# POWER.net
KiCad netlist of a schematic drawn in Altium Designer
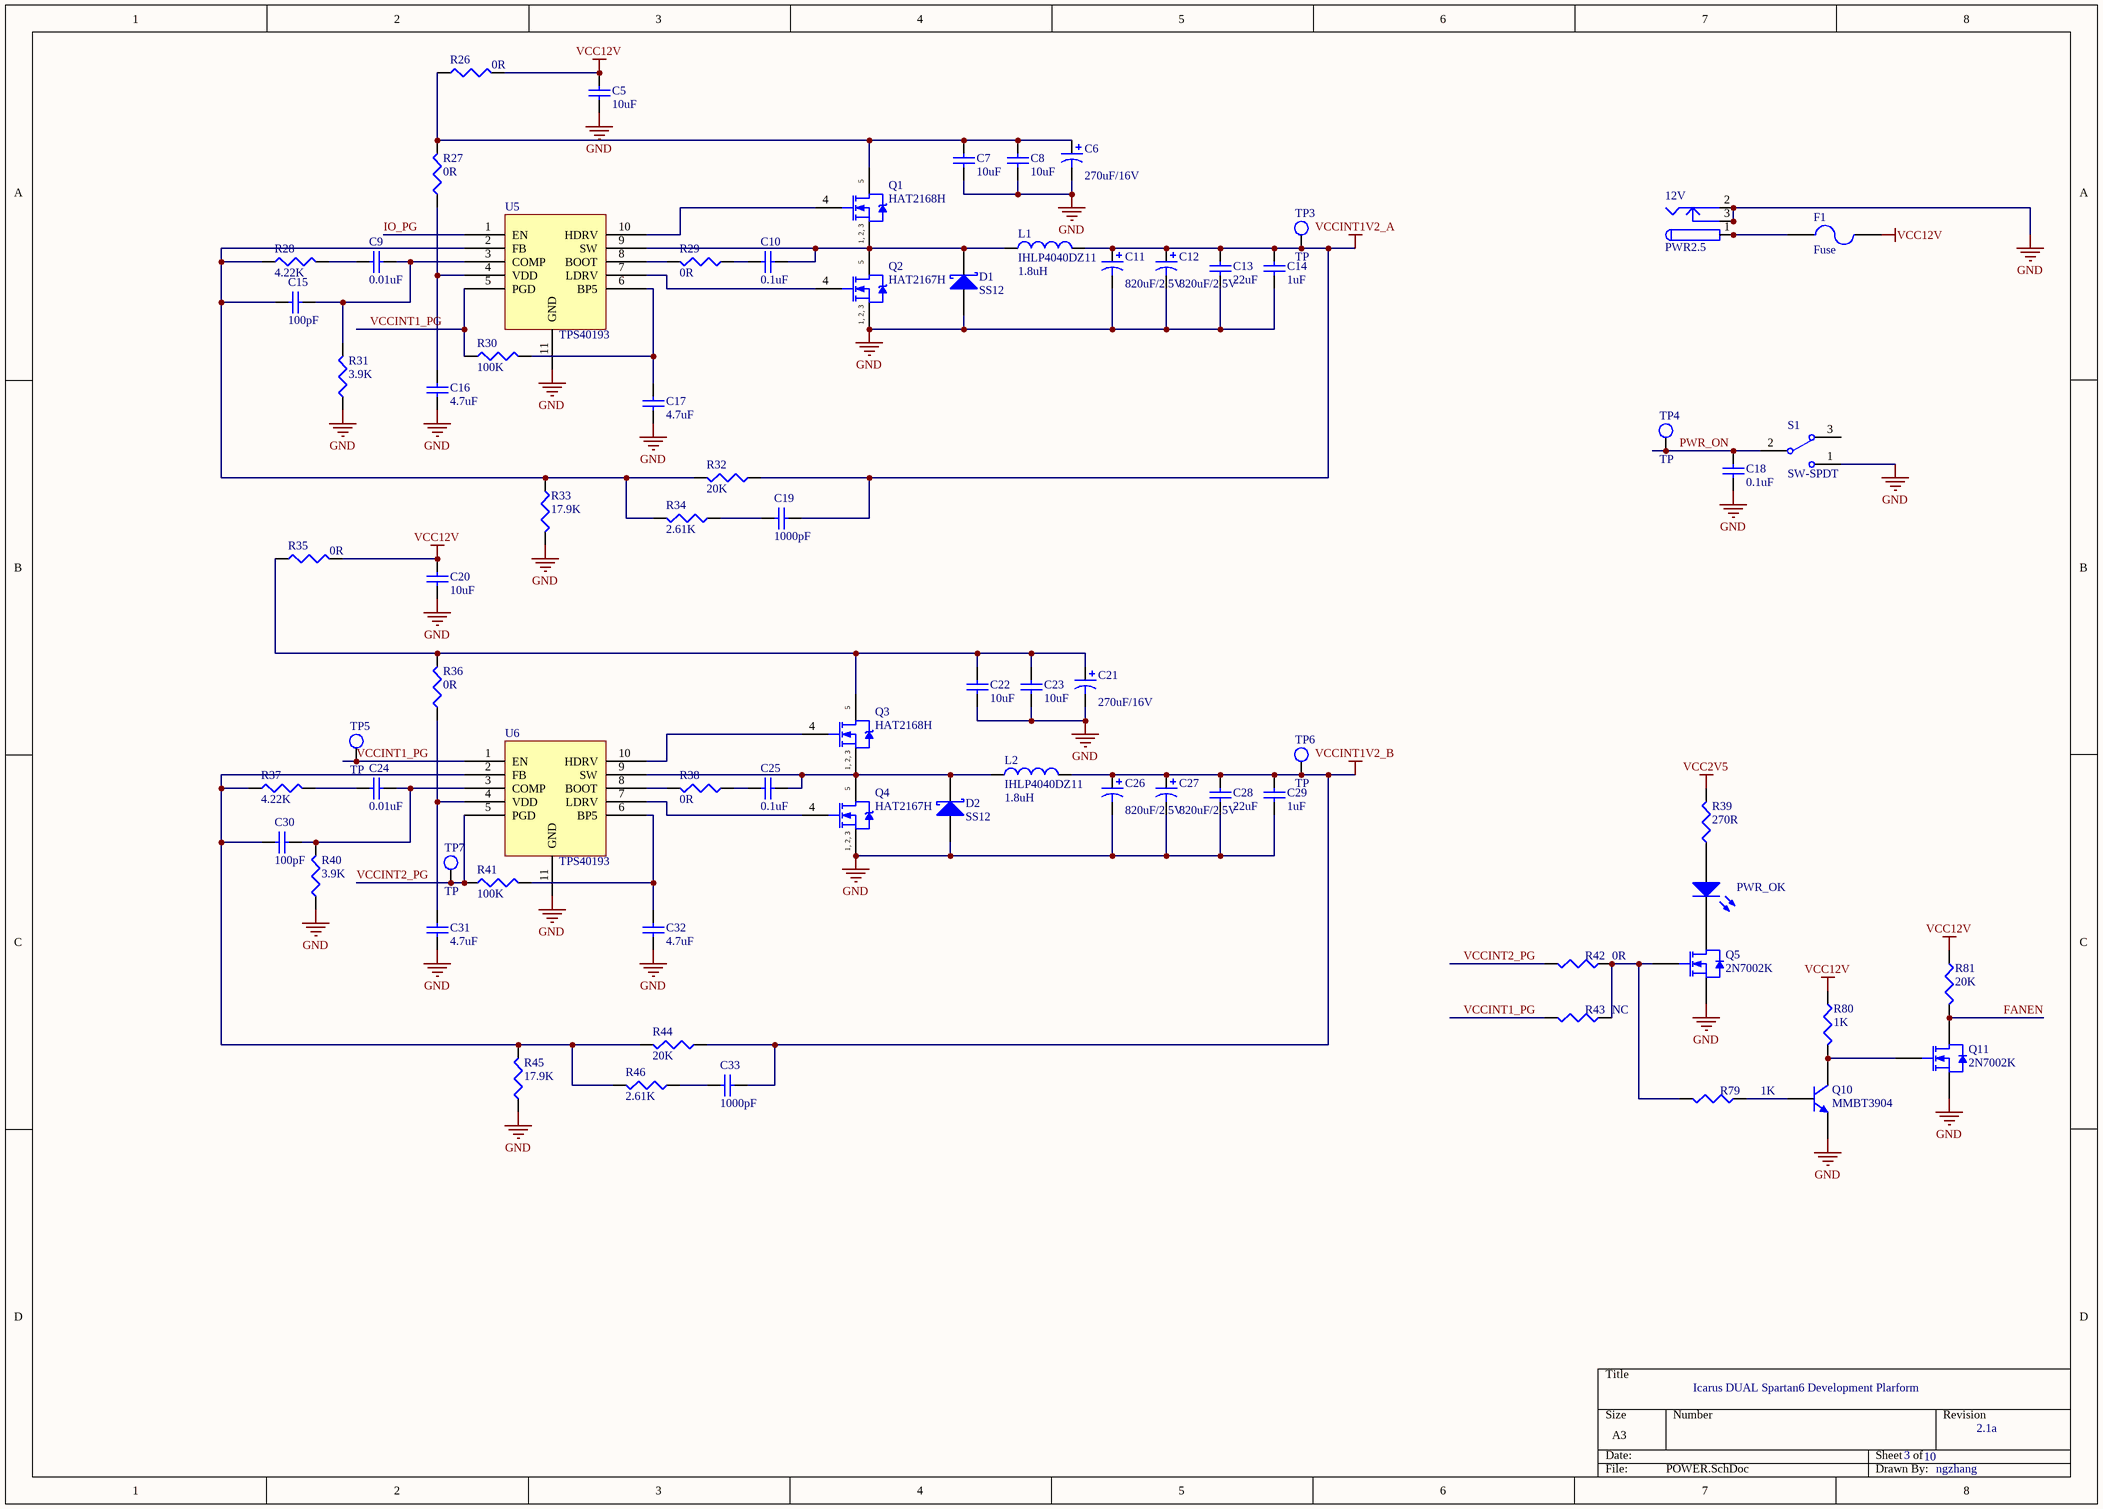
[diagram p0: POWER.SchDoc]

(export (version "E")
  (design (tool "Eeschema 10.0.6"))
  (components
    (comp (ref "12V")
      (value "PWR2.5")
      (footprint "KLD-0202")
      (description "Low Voltage Power Supply Connector")
      (fields (field (name "PUBLISHER") "Altium Limited"))
      (libsource (lib "Miscellaneous Connectors") (part "PWR2.5"))
    )
    (comp (ref "C5")
      (value "10uF")
      (footprint "C1206")
      (description "Capacitor (Semiconductor SIM Model)")
      (fields (field (name "PUBLISHER") "Altium Limited"))
      (libsource (lib "Miscellaneous Devices") (part "Cap Semi"))
    )
    (comp (ref "C6")
      (value "270uF/16V")
      (footprint "CAP8X8")
      (description "Polarized Capacitor (Radial)")
      (fields (field (name "PUBLISHER") "Altium Limited"))
      (libsource (lib "Miscellaneous Devices") (part "Cap Pol1"))
    )
    (comp (ref "C7")
      (value "10uF")
      (footprint "C1206")
      (description "Capacitor (Semiconductor SIM Model)")
      (fields (field (name "PUBLISHER") "Altium Limited"))
      (libsource (lib "Miscellaneous Devices") (part "Cap Semi"))
    )
    (comp (ref "C8")
      (value "10uF")
      (footprint "C1206")
      (description "Capacitor (Semiconductor SIM Model)")
      (fields (field (name "PUBLISHER") "Altium Limited"))
      (libsource (lib "Miscellaneous Devices") (part "Cap Semi"))
    )
    (comp (ref "C9")
      (value "0.01uF")
      (footprint "1608[0603]")
      (description "Capacitor (Semiconductor SIM Model)")
      (fields (field (name "PUBLISHER") "Altium Limited"))
      (libsource (lib "Miscellaneous Devices") (part "Cap Semi"))
    )
    (comp (ref "C10")
      (value "0.1uF")
      (footprint "1608[0603]")
      (description "Capacitor (Semiconductor SIM Model)")
      (fields (field (name "PUBLISHER") "Altium Limited"))
      (libsource (lib "Miscellaneous Devices") (part "Cap Semi"))
    )
    (comp (ref "C11")
      (value "820uF/2.5V")
      (footprint "CAP8X8")
      (description "Polarized Capacitor (Radial)")
      (fields (field (name "PUBLISHER") "Altium Limited"))
      (libsource (lib "Miscellaneous Devices") (part "Cap Pol1"))
    )
    (comp (ref "C12")
      (value "820uF/2.5V")
      (footprint "CAP8X8")
      (description "Polarized Capacitor (Radial)")
      (fields (field (name "PUBLISHER") "Altium Limited"))
      (libsource (lib "Miscellaneous Devices") (part "Cap Pol1"))
    )
    (comp (ref "C13")
      (value "22uF")
      (footprint "C1206")
      (description "Capacitor (Semiconductor SIM Model)")
      (fields (field (name "PUBLISHER") "Altium Limited"))
      (libsource (lib "Miscellaneous Devices") (part "Cap Semi"))
    )
    (comp (ref "C14")
      (value "1uF")
      (footprint "1608[0603]")
      (description "Capacitor (Semiconductor SIM Model)")
      (fields (field (name "PUBLISHER") "Altium Limited"))
      (libsource (lib "Miscellaneous Devices") (part "Cap Semi"))
    )
    (comp (ref "C15")
      (value "100pF")
      (footprint "1608[0603]")
      (description "Capacitor (Semiconductor SIM Model)")
      (fields (field (name "PUBLISHER") "Altium Limited"))
      (libsource (lib "Miscellaneous Devices") (part "Cap Semi"))
    )
    (comp (ref "C16")
      (value "4.7uF")
      (footprint "C0805")
      (description "Capacitor (Semiconductor SIM Model)")
      (fields (field (name "PUBLISHER") "Altium Limited"))
      (libsource (lib "Miscellaneous Devices") (part "Cap Semi"))
    )
    (comp (ref "C17")
      (value "4.7uF")
      (footprint "C0805")
      (description "Capacitor (Semiconductor SIM Model)")
      (fields (field (name "PUBLISHER") "Altium Limited"))
      (libsource (lib "Miscellaneous Devices") (part "Cap Semi"))
    )
    (comp (ref "C18")
      (value "0.1uF")
      (footprint "1608[0603]")
      (description "Capacitor (Semiconductor SIM Model)")
      (fields (field (name "PUBLISHER") "Altium Limited"))
      (libsource (lib "Miscellaneous Devices") (part "Cap Semi"))
    )
    (comp (ref "C19")
      (value "1000pF")
      (footprint "1608[0603]")
      (description "Capacitor (Semiconductor SIM Model)")
      (fields (field (name "PUBLISHER") "Altium Limited"))
      (libsource (lib "Miscellaneous Devices") (part "Cap Semi"))
    )
    (comp (ref "C20")
      (value "10uF")
      (footprint "C1206")
      (description "Capacitor (Semiconductor SIM Model)")
      (fields (field (name "PUBLISHER") "Altium Limited"))
      (libsource (lib "Miscellaneous Devices") (part "Cap Semi"))
    )
    (comp (ref "C21")
      (value "270uF/16V")
      (footprint "CAP8X8")
      (description "Polarized Capacitor (Radial)")
      (fields (field (name "PUBLISHER") "Altium Limited"))
      (libsource (lib "Miscellaneous Devices") (part "Cap Pol1"))
    )
    (comp (ref "C22")
      (value "10uF")
      (footprint "C1206")
      (description "Capacitor (Semiconductor SIM Model)")
      (fields (field (name "PUBLISHER") "Altium Limited"))
      (libsource (lib "Miscellaneous Devices") (part "Cap Semi"))
    )
    (comp (ref "C23")
      (value "10uF")
      (footprint "C1206")
      (description "Capacitor (Semiconductor SIM Model)")
      (fields (field (name "PUBLISHER") "Altium Limited"))
      (libsource (lib "Miscellaneous Devices") (part "Cap Semi"))
    )
    (comp (ref "C24")
      (value "0.01uF")
      (footprint "1608[0603]")
      (description "Capacitor (Semiconductor SIM Model)")
      (fields (field (name "PUBLISHER") "Altium Limited"))
      (libsource (lib "Miscellaneous Devices") (part "Cap Semi"))
    )
    (comp (ref "C25")
      (value "0.1uF")
      (footprint "1608[0603]")
      (description "Capacitor (Semiconductor SIM Model)")
      (fields (field (name "PUBLISHER") "Altium Limited"))
      (libsource (lib "Miscellaneous Devices") (part "Cap Semi"))
    )
    (comp (ref "C26")
      (value "820uF/2.5V")
      (footprint "CAP8X8")
      (description "Polarized Capacitor (Radial)")
      (fields (field (name "PUBLISHER") "Altium Limited"))
      (libsource (lib "Miscellaneous Devices") (part "Cap Pol1"))
    )
    (comp (ref "C27")
      (value "820uF/2.5V")
      (footprint "CAP8X8")
      (description "Polarized Capacitor (Radial)")
      (fields (field (name "PUBLISHER") "Altium Limited"))
      (libsource (lib "Miscellaneous Devices") (part "Cap Pol1"))
    )
    (comp (ref "C28")
      (value "22uF")
      (footprint "C1206")
      (description "Capacitor (Semiconductor SIM Model)")
      (fields (field (name "PUBLISHER") "Altium Limited"))
      (libsource (lib "Miscellaneous Devices") (part "Cap Semi"))
    )
    (comp (ref "C29")
      (value "1uF")
      (footprint "1608[0603]")
      (description "Capacitor (Semiconductor SIM Model)")
      (fields (field (name "PUBLISHER") "Altium Limited"))
      (libsource (lib "Miscellaneous Devices") (part "Cap Semi"))
    )
    (comp (ref "C30")
      (value "100pF")
      (footprint "1608[0603]")
      (description "Capacitor (Semiconductor SIM Model)")
      (fields (field (name "PUBLISHER") "Altium Limited"))
      (libsource (lib "Miscellaneous Devices") (part "Cap Semi"))
    )
    (comp (ref "C31")
      (value "4.7uF")
      (footprint "C0805")
      (description "Capacitor (Semiconductor SIM Model)")
      (fields (field (name "PUBLISHER") "Altium Limited"))
      (libsource (lib "Miscellaneous Devices") (part "Cap Semi"))
    )
    (comp (ref "C32")
      (value "4.7uF")
      (footprint "C0805")
      (description "Capacitor (Semiconductor SIM Model)")
      (fields (field (name "PUBLISHER") "Altium Limited"))
      (libsource (lib "Miscellaneous Devices") (part "Cap Semi"))
    )
    (comp (ref "C33")
      (value "1000pF")
      (footprint "1608[0603]")
      (description "Capacitor (Semiconductor SIM Model)")
      (fields (field (name "PUBLISHER") "Altium Limited"))
      (libsource (lib "Miscellaneous Devices") (part "Cap Semi"))
    )
    (comp (ref "D1")
      (value "SS12")
      (footprint "SMA")
      (description "Schottky Rectifier")
      (fields (field (name "PUBLISHER") "Altium Limited"))
      (libsource (lib "IR Rectifier - Schottky") (part "10MQ060N"))
    )
    (comp (ref "D2")
      (value "SS12")
      (footprint "SMA")
      (description "Schottky Rectifier")
      (fields (field (name "PUBLISHER") "Altium Limited"))
      (libsource (lib "IR Rectifier - Schottky") (part "10MQ060N"))
    )
    (comp (ref "F1")
      (value "Fuse")
      (footprint "12Z-2010")
      (fields (field (name "PUBLISHER") "Altium Limited"))
      (libsource (lib "Miscellaneous Devices") (part "Fuse 2"))
    )
    (comp (ref "L1")
      (value "IHLP4040DZ11")
      (footprint "IHLP4040")
      (description "Inductor")
      (fields (field (name "ALTIUM_VALUE") "1.8uH") (field (name "PUBLISHER") "Altium Limited"))
      (libsource (lib "Miscellaneous Devices") (part "Inductor"))
    )
    (comp (ref "L2")
      (value "IHLP4040DZ11")
      (footprint "IHLP4040")
      (description "Inductor")
      (fields (field (name "ALTIUM_VALUE") "1.8uH") (field (name "PUBLISHER") "Altium Limited"))
      (libsource (lib "Miscellaneous Devices") (part "Inductor"))
    )
    (comp (ref "PWR_OK")
      (value "LED3")
      (footprint "CD1608-0603")
      (description "Typical BLUE SiC LED")
      (fields (field (name "PUBLISHER") "Altium Limited"))
      (libsource (lib "Miscellaneous Devices") (part "LED3"))
    )
    (comp (ref "Q1") (value "HAT2168H") (footprint "LFPAK") (libsource (lib "S6") (part "HAT216X")))
    (comp (ref "Q2") (value "HAT2167H") (footprint "LFPAK") (libsource (lib "S6") (part "HAT216X")))
    (comp (ref "Q3") (value "HAT2168H") (footprint "LFPAK") (libsource (lib "S6") (part "HAT216X")))
    (comp (ref "Q4") (value "HAT2167H") (footprint "LFPAK") (libsource (lib "S6") (part "HAT216X")))
    (comp (ref "Q5")
      (value "2N7002K")
      (footprint "SOT23_N")
      (description "N-channel Enhancement Mode Field-effect Transistor")
      (fields (field (name "PUBLISHER") "Altium Limited"))
      (libsource (lib "Philips Discrete MOSFET - Low Power") (part "2N7002"))
    )
    (comp (ref "Q10")
      (value "MMBT3904")
      (footprint "SOT23_N")
      (description "NPN Switching Transistor")
      (fields (field (name "PUBLISHER") "Altium Limited"))
      (libsource (lib "Philips Discrete BJT - Low Power") (part "MMBT3904"))
    )
    (comp (ref "Q11")
      (value "2N7002K")
      (footprint "SOT23_N")
      (description "N-channel Enhancement Mode Field-effect Transistor")
      (fields (field (name "PUBLISHER") "Altium Limited"))
      (libsource (lib "Philips Discrete MOSFET - Low Power") (part "2N7002"))
    )
    (comp (ref "R26")
      (value "0R")
      (footprint "C1206")
      (description "Resistor")
      (fields (field (name "PUBLISHER") "Altium Limited"))
      (libsource (lib "Miscellaneous Devices") (part "Res3"))
    )
    (comp (ref "R27")
      (value "0R")
      (footprint "J1-0603")
      (description "Resistor")
      (fields (field (name "PUBLISHER") "Altium Limited"))
      (libsource (lib "Miscellaneous Devices") (part "Res3"))
    )
    (comp (ref "R28")
      (value "4.22K")
      (footprint "J1-0603")
      (description "Resistor")
      (fields (field (name "PUBLISHER") "Altium Limited"))
      (libsource (lib "Miscellaneous Devices") (part "Res3"))
    )
    (comp (ref "R29")
      (value "0R")
      (footprint "J1-0603")
      (description "Resistor")
      (fields (field (name "PUBLISHER") "Altium Limited"))
      (libsource (lib "Miscellaneous Devices") (part "Res3"))
    )
    (comp (ref "R30")
      (value "100K")
      (footprint "J1-0603")
      (description "Resistor")
      (fields (field (name "PUBLISHER") "Altium Limited"))
      (libsource (lib "Miscellaneous Devices") (part "Res3"))
    )
    (comp (ref "R31")
      (value "3.9K")
      (footprint "J1-0603")
      (description "Resistor")
      (fields (field (name "PUBLISHER") "Altium Limited"))
      (libsource (lib "Miscellaneous Devices") (part "Res3"))
    )
    (comp (ref "R32")
      (value "20K")
      (footprint "J1-0603")
      (description "Resistor")
      (fields (field (name "PUBLISHER") "Altium Limited"))
      (libsource (lib "Miscellaneous Devices") (part "Res3"))
    )
    (comp (ref "R33")
      (value "17.9K")
      (footprint "J1-0603")
      (description "Resistor")
      (fields (field (name "PUBLISHER") "Altium Limited"))
      (libsource (lib "Miscellaneous Devices") (part "Res3"))
    )
    (comp (ref "R34")
      (value "2.61K")
      (footprint "J1-0603")
      (description "Resistor")
      (fields (field (name "PUBLISHER") "Altium Limited"))
      (libsource (lib "Miscellaneous Devices") (part "Res3"))
    )
    (comp (ref "R35")
      (value "0R")
      (footprint "C1206")
      (description "Resistor")
      (fields (field (name "PUBLISHER") "Altium Limited"))
      (libsource (lib "Miscellaneous Devices") (part "Res3"))
    )
    (comp (ref "R36")
      (value "0R")
      (footprint "J1-0603")
      (description "Resistor")
      (fields (field (name "PUBLISHER") "Altium Limited"))
      (libsource (lib "Miscellaneous Devices") (part "Res3"))
    )
    (comp (ref "R37")
      (value "4.22K")
      (footprint "J1-0603")
      (description "Resistor")
      (fields (field (name "PUBLISHER") "Altium Limited"))
      (libsource (lib "Miscellaneous Devices") (part "Res3"))
    )
    (comp (ref "R38")
      (value "0R")
      (footprint "J1-0603")
      (description "Resistor")
      (fields (field (name "PUBLISHER") "Altium Limited"))
      (libsource (lib "Miscellaneous Devices") (part "Res3"))
    )
    (comp (ref "R39")
      (value "270R")
      (footprint "J1-0603")
      (description "Resistor")
      (fields (field (name "PUBLISHER") "Altium Limited"))
      (libsource (lib "Miscellaneous Devices") (part "Res3"))
    )
    (comp (ref "R40")
      (value "3.9K")
      (footprint "J1-0603")
      (description "Resistor")
      (fields (field (name "PUBLISHER") "Altium Limited"))
      (libsource (lib "Miscellaneous Devices") (part "Res3"))
    )
    (comp (ref "R41")
      (value "100K")
      (footprint "J1-0603")
      (description "Resistor")
      (fields (field (name "PUBLISHER") "Altium Limited"))
      (libsource (lib "Miscellaneous Devices") (part "Res3"))
    )
    (comp (ref "R42")
      (value "0R")
      (footprint "J1-0603")
      (description "Resistor")
      (fields (field (name "PUBLISHER") "Altium Limited"))
      (libsource (lib "Miscellaneous Devices") (part "Res3"))
    )
    (comp (ref "R43")
      (value "NC")
      (footprint "J1-0603")
      (description "Resistor")
      (fields (field (name "PUBLISHER") "Altium Limited"))
      (libsource (lib "Miscellaneous Devices") (part "Res3"))
    )
    (comp (ref "R44")
      (value "20K")
      (footprint "J1-0603")
      (description "Resistor")
      (fields (field (name "PUBLISHER") "Altium Limited"))
      (libsource (lib "Miscellaneous Devices") (part "Res3"))
    )
    (comp (ref "R45")
      (value "17.9K")
      (footprint "J1-0603")
      (description "Resistor")
      (fields (field (name "PUBLISHER") "Altium Limited"))
      (libsource (lib "Miscellaneous Devices") (part "Res3"))
    )
    (comp (ref "R46")
      (value "2.61K")
      (footprint "J1-0603")
      (description "Resistor")
      (fields (field (name "PUBLISHER") "Altium Limited"))
      (libsource (lib "Miscellaneous Devices") (part "Res3"))
    )
    (comp (ref "R79")
      (value "1K")
      (footprint "J1-0603")
      (description "Resistor")
      (fields (field (name "PUBLISHER") "Altium Limited"))
      (libsource (lib "Miscellaneous Devices") (part "Res3"))
    )
    (comp (ref "R80")
      (value "1K")
      (footprint "J1-0603")
      (description "Resistor")
      (fields (field (name "PUBLISHER") "Altium Limited"))
      (libsource (lib "Miscellaneous Devices") (part "Res3"))
    )
    (comp (ref "R81")
      (value "20K")
      (footprint "J1-0603")
      (description "Resistor")
      (fields (field (name "PUBLISHER") "Altium Limited"))
      (libsource (lib "Miscellaneous Devices") (part "Res3"))
    )
    (comp (ref "S1")
      (value "SW-SPDT")
      (footprint "SW_3")
      (description "SPDT Subminiature Toggle Switch, Right Angle Mounting, Vertical Actuation")
      (fields (field (name "PUBLISHER") "Altium Limited"))
      (libsource (lib "Miscellaneous Devices") (part "SW-SPDT"))
    )
    (comp (ref "TP3") (value "TP") (footprint "TP") (libsource (lib "S6") (part "TP")))
    (comp (ref "TP4") (value "TP") (footprint "TP") (libsource (lib "S6") (part "TP")))
    (comp (ref "TP5") (value "TP") (footprint "TP") (libsource (lib "S6") (part "TP")))
    (comp (ref "TP6") (value "TP") (footprint "TP") (libsource (lib "S6") (part "TP")))
    (comp (ref "TP7") (value "TP") (footprint "TP") (libsource (lib "S6") (part "TP")))
    (comp (ref "U5") (value "TPS40193") (footprint "SON10") (libsource (lib "S6") (part "TPS40193")))
    (comp (ref "U6") (value "TPS40193") (footprint "SON10") (libsource (lib "S6") (part "TPS40193")))
  )
  (nets
    (net (code "1") (name "/FANEN") (class "Default")
      (node (ref "Q11") (pin "3") (pinfunction "D_3") (pintype "passive"))
      (node (ref "R81") (pin "2") (pinfunction "2_2") (pintype "passive"))
    )
    (net (code "2") (name "/IO_PG") (class "Default")
      (node (ref "U5") (pin "1") (pinfunction "EN_1") (pintype "passive"))
    )
    (net (code "3") (name "/PWR_ON") (class "Default")
      (node (ref "C18") (pin "2") (pinfunction "2_2") (pintype "passive"))
      (node (ref "S1") (pin "2") (pinfunction "2_2") (pintype "passive"))
      (node (ref "TP4") (pin "1") (pinfunction "TP_1") (pintype "passive"))
    )
    (net (code "4") (name "/VCCINT1_PG") (class "Default")
      (node (ref "R30") (pin "1") (pinfunction "1_1") (pintype "passive"))
      (node (ref "R43") (pin "2") (pinfunction "2_2") (pintype "passive"))
      (node (ref "TP5") (pin "1") (pinfunction "TP_1") (pintype "passive"))
      (node (ref "U5") (pin "5") (pinfunction "PGD_5") (pintype "passive"))
      (node (ref "U6") (pin "1") (pinfunction "EN_1") (pintype "passive"))
    )
    (net (code "5") (name "/VCCINT2_PG") (class "Default")
      (node (ref "R41") (pin "1") (pinfunction "1_1") (pintype "passive"))
      (node (ref "R42") (pin "2") (pinfunction "2_2") (pintype "passive"))
      (node (ref "TP7") (pin "1") (pinfunction "TP_1") (pintype "passive"))
      (node (ref "U6") (pin "5") (pinfunction "PGD_5") (pintype "passive"))
    )
    (net (code "6") (name "GND") (class "Default")
      (node (ref "12V") (pin "2") (pinfunction "2_2") (pintype "power_in"))
      (node (ref "12V") (pin "2A") (pinfunction "2A_2A") (pintype "power_in"))
      (node (ref "12V") (pin "2B") (pinfunction "2B_2B") (pintype "power_in"))
      (node (ref "12V") (pin "3") (pinfunction "3_3") (pintype "power_in"))
      (node (ref "12V") (pin "3A") (pinfunction "3A_3A") (pintype "power_in"))
      (node (ref "12V") (pin "3B") (pinfunction "3B_3B") (pintype "power_in"))
      (node (ref "C11") (pin "2") (pinfunction "2_2") (pintype "passive"))
      (node (ref "C12") (pin "2") (pinfunction "2_2") (pintype "passive"))
      (node (ref "C13") (pin "1") (pinfunction "1_1") (pintype "passive"))
      (node (ref "C14") (pin "1") (pinfunction "1_1") (pintype "passive"))
      (node (ref "C16") (pin "2") (pinfunction "2_2") (pintype "passive"))
      (node (ref "C17") (pin "1") (pinfunction "1_1") (pintype "passive"))
      (node (ref "C18") (pin "1") (pinfunction "1_1") (pintype "passive"))
      (node (ref "C20") (pin "1") (pinfunction "1_1") (pintype "passive"))
      (node (ref "C21") (pin "2") (pinfunction "2_2") (pintype "passive"))
      (node (ref "C22") (pin "1") (pinfunction "1_1") (pintype "passive"))
      (node (ref "C23") (pin "1") (pinfunction "1_1") (pintype "passive"))
      (node (ref "C26") (pin "2") (pinfunction "2_2") (pintype "passive"))
      (node (ref "C27") (pin "2") (pinfunction "2_2") (pintype "passive"))
      (node (ref "C28") (pin "1") (pinfunction "1_1") (pintype "passive"))
      (node (ref "C29") (pin "1") (pinfunction "1_1") (pintype "passive"))
      (node (ref "C31") (pin "1") (pinfunction "1_1") (pintype "passive"))
      (node (ref "C32") (pin "2") (pinfunction "2_2") (pintype "passive"))
      (node (ref "C5") (pin "1") (pinfunction "1_1") (pintype "passive"))
      (node (ref "C6") (pin "2") (pinfunction "2_2") (pintype "passive"))
      (node (ref "C7") (pin "1") (pinfunction "1_1") (pintype "passive"))
      (node (ref "C8") (pin "1") (pinfunction "1_1") (pintype "passive"))
      (node (ref "D1") (pin "1") (pinfunction "A_1") (pintype "passive"))
      (node (ref "D2") (pin "1") (pinfunction "A_1") (pintype "passive"))
      (node (ref "Q10") (pin "2") (pinfunction "E_2") (pintype "passive"))
      (node (ref "Q11") (pin "2") (pinfunction "S_2") (pintype "passive"))
      (node (ref "Q2") (pin "1") (pinfunction "S_1") (pintype "passive"))
      (node (ref "Q2") (pin "2") (pinfunction "S_2") (pintype "passive"))
      (node (ref "Q2") (pin "3") (pinfunction "S_3") (pintype "passive"))
      (node (ref "Q4") (pin "1") (pinfunction "S_1") (pintype "passive"))
      (node (ref "Q4") (pin "2") (pinfunction "S_2") (pintype "passive"))
      (node (ref "Q4") (pin "3") (pinfunction "S_3") (pintype "passive"))
      (node (ref "Q5") (pin "2") (pinfunction "S_2") (pintype "passive"))
      (node (ref "R31") (pin "1") (pinfunction "1_1") (pintype "passive"))
      (node (ref "R33") (pin "2") (pinfunction "2_2") (pintype "passive"))
      (node (ref "R40") (pin "1") (pinfunction "1_1") (pintype "passive"))
      (node (ref "R45") (pin "1") (pinfunction "1_1") (pintype "passive"))
      (node (ref "S1") (pin "1") (pinfunction "1_1") (pintype "passive"))
      (node (ref "U5") (pin "11") (pinfunction "GND_11") (pintype "passive"))
      (node (ref "U6") (pin "11") (pinfunction "GND_11") (pintype "passive"))
    )
    (net (code "7") (name "Net-(12V-Pad1)") (class "Default")
      (node (ref "12V") (pin "1") (pinfunction "1_1") (pintype "power_in"))
      (node (ref "12V") (pin "1A") (pinfunction "1A_1A") (pintype "power_in"))
      (node (ref "12V") (pin "1B") (pinfunction "1B_1B") (pintype "power_in"))
      (node (ref "F1") (pin "1") (pinfunction "1_1") (pintype "passive"))
    )
    (net (code "8") (name "Net-(C9-Pad2)") (class "Default")
      (node (ref "C9") (pin "2") (pinfunction "2_2") (pintype "passive"))
      (node (ref "R28") (pin "2") (pinfunction "2_2") (pintype "passive"))
    )
    (net (code "9") (name "Net-(C10-Pad2)") (class "Default")
      (node (ref "C10") (pin "2") (pinfunction "2_2") (pintype "passive"))
      (node (ref "R29") (pin "1") (pinfunction "1_1") (pintype "passive"))
    )
    (net (code "10") (name "Net-(C19-Pad1)") (class "Default")
      (node (ref "C19") (pin "1") (pinfunction "1_1") (pintype "passive"))
      (node (ref "R34") (pin "1") (pinfunction "1_1") (pintype "passive"))
    )
    (net (code "11") (name "Net-(C24-Pad2)") (class "Default")
      (node (ref "C24") (pin "2") (pinfunction "2_2") (pintype "passive"))
      (node (ref "R37") (pin "2") (pinfunction "2_2") (pintype "passive"))
    )
    (net (code "12") (name "Net-(C25-Pad2)") (class "Default")
      (node (ref "C25") (pin "2") (pinfunction "2_2") (pintype "passive"))
      (node (ref "R38") (pin "1") (pinfunction "1_1") (pintype "passive"))
    )
    (net (code "13") (name "Net-(C33-Pad1)") (class "Default")
      (node (ref "C33") (pin "1") (pinfunction "1_1") (pintype "passive"))
      (node (ref "R46") (pin "1") (pinfunction "1_1") (pintype "passive"))
    )
    (net (code "14") (name "Net-(D1-K)") (class "Default")
      (node (ref "C10") (pin "1") (pinfunction "1_1") (pintype "passive"))
      (node (ref "D1") (pin "2") (pinfunction "K_2") (pintype "passive"))
      (node (ref "L1") (pin "1") (pinfunction "1_1") (pintype "passive"))
      (node (ref "Q1") (pin "1") (pinfunction "S_1") (pintype "passive"))
      (node (ref "Q1") (pin "2") (pinfunction "S_2") (pintype "passive"))
      (node (ref "Q1") (pin "3") (pinfunction "S_3") (pintype "passive"))
      (node (ref "Q2") (pin "5") (pinfunction "D_5") (pintype "passive"))
      (node (ref "U5") (pin "9") (pinfunction "SW_9") (pintype "passive"))
    )
    (net (code "15") (name "Net-(D2-K)") (class "Default")
      (node (ref "C25") (pin "1") (pinfunction "1_1") (pintype "passive"))
      (node (ref "D2") (pin "2") (pinfunction "K_2") (pintype "passive"))
      (node (ref "L2") (pin "1") (pinfunction "1_1") (pintype "passive"))
      (node (ref "Q3") (pin "1") (pinfunction "S_1") (pintype "passive"))
      (node (ref "Q3") (pin "2") (pinfunction "S_2") (pintype "passive"))
      (node (ref "Q3") (pin "3") (pinfunction "S_3") (pintype "passive"))
      (node (ref "Q4") (pin "5") (pinfunction "D_5") (pintype "passive"))
      (node (ref "U6") (pin "9") (pinfunction "SW_9") (pintype "passive"))
    )
    (net (code "16") (name "Net-(PWR_OK-A)") (class "Default")
      (node (ref "PWR_OK") (pin "1") (pinfunction "A_1") (pintype "passive"))
      (node (ref "R39") (pin "1") (pinfunction "1_1") (pintype "passive"))
    )
    (net (code "17") (name "Net-(PWR_OK-K)") (class "Default")
      (node (ref "PWR_OK") (pin "2") (pinfunction "K_2") (pintype "passive"))
      (node (ref "Q5") (pin "3") (pinfunction "D_3") (pintype "passive"))
    )
    (net (code "18") (name "Net-(Q1-D)") (class "Default")
      (node (ref "C6") (pin "1") (pinfunction "1_1") (pintype "passive"))
      (node (ref "C7") (pin "2") (pinfunction "2_2") (pintype "passive"))
      (node (ref "C8") (pin "2") (pinfunction "2_2") (pintype "passive"))
      (node (ref "Q1") (pin "5") (pinfunction "D_5") (pintype "passive"))
      (node (ref "R26") (pin "1") (pinfunction "1_1") (pintype "passive"))
      (node (ref "R27") (pin "2") (pinfunction "2_2") (pintype "passive"))
    )
    (net (code "19") (name "Net-(Q1-G)") (class "Default")
      (node (ref "Q1") (pin "4") (pinfunction "G_4") (pintype "passive"))
      (node (ref "U5") (pin "10") (pinfunction "HDRV_10") (pintype "passive"))
    )
    (net (code "20") (name "Net-(Q2-G)") (class "Default")
      (node (ref "Q2") (pin "4") (pinfunction "G_4") (pintype "passive"))
      (node (ref "U5") (pin "7") (pinfunction "LDRV_7") (pintype "passive"))
    )
    (net (code "21") (name "Net-(Q3-D)") (class "Default")
      (node (ref "C21") (pin "1") (pinfunction "1_1") (pintype "passive"))
      (node (ref "C22") (pin "2") (pinfunction "2_2") (pintype "passive"))
      (node (ref "C23") (pin "2") (pinfunction "2_2") (pintype "passive"))
      (node (ref "Q3") (pin "5") (pinfunction "D_5") (pintype "passive"))
      (node (ref "R35") (pin "1") (pinfunction "1_1") (pintype "passive"))
      (node (ref "R36") (pin "2") (pinfunction "2_2") (pintype "passive"))
    )
    (net (code "22") (name "Net-(Q3-G)") (class "Default")
      (node (ref "Q3") (pin "4") (pinfunction "G_4") (pintype "passive"))
      (node (ref "U6") (pin "10") (pinfunction "HDRV_10") (pintype "passive"))
    )
    (net (code "23") (name "Net-(Q4-G)") (class "Default")
      (node (ref "Q4") (pin "4") (pinfunction "G_4") (pintype "passive"))
      (node (ref "U6") (pin "7") (pinfunction "LDRV_7") (pintype "passive"))
    )
    (net (code "24") (name "Net-(Q5-G)") (class "Default")
      (node (ref "Q5") (pin "1") (pinfunction "G_1") (pintype "passive"))
      (node (ref "R42") (pin "1") (pinfunction "1_1") (pintype "passive"))
      (node (ref "R43") (pin "1") (pinfunction "1_1") (pintype "passive"))
      (node (ref "R79") (pin "2") (pinfunction "2_2") (pintype "passive"))
    )
    (net (code "25") (name "Net-(Q10-B)") (class "Default")
      (node (ref "Q10") (pin "1") (pinfunction "B_1") (pintype "passive"))
      (node (ref "R79") (pin "1") (pinfunction "1_1") (pintype "passive"))
    )
    (net (code "26") (name "Net-(Q10-C)") (class "Default")
      (node (ref "Q10") (pin "3") (pinfunction "C_3") (pintype "passive"))
      (node (ref "Q11") (pin "1") (pinfunction "G_1") (pintype "passive"))
      (node (ref "R80") (pin "2") (pinfunction "2_2") (pintype "passive"))
    )
    (net (code "27") (name "Net-(U5-BOOT)") (class "Default")
      (node (ref "R29") (pin "2") (pinfunction "2_2") (pintype "passive"))
      (node (ref "U5") (pin "8") (pinfunction "BOOT_8") (pintype "passive"))
    )
    (net (code "28") (name "Net-(U5-BP5)") (class "Default")
      (node (ref "C17") (pin "2") (pinfunction "2_2") (pintype "passive"))
      (node (ref "R30") (pin "2") (pinfunction "2_2") (pintype "passive"))
      (node (ref "U5") (pin "6") (pinfunction "BP5_6") (pintype "passive"))
    )
    (net (code "29") (name "Net-(U5-COMP)") (class "Default")
      (node (ref "C15") (pin "1") (pinfunction "1_1") (pintype "passive"))
      (node (ref "C9") (pin "1") (pinfunction "1_1") (pintype "passive"))
      (node (ref "R31") (pin "2") (pinfunction "2_2") (pintype "passive"))
      (node (ref "U5") (pin "3") (pinfunction "COMP_3") (pintype "passive"))
    )
    (net (code "30") (name "Net-(U5-FB)") (class "Default")
      (node (ref "C15") (pin "2") (pinfunction "2_2") (pintype "passive"))
      (node (ref "R28") (pin "1") (pinfunction "1_1") (pintype "passive"))
      (node (ref "R32") (pin "2") (pinfunction "2_2") (pintype "passive"))
      (node (ref "R33") (pin "1") (pinfunction "1_1") (pintype "passive"))
      (node (ref "R34") (pin "2") (pinfunction "2_2") (pintype "passive"))
      (node (ref "U5") (pin "2") (pinfunction "FB_2") (pintype "passive"))
    )
    (net (code "31") (name "Net-(U5-VDD)") (class "Default")
      (node (ref "C16") (pin "1") (pinfunction "1_1") (pintype "passive"))
      (node (ref "R27") (pin "1") (pinfunction "1_1") (pintype "passive"))
      (node (ref "U5") (pin "4") (pinfunction "VDD_4") (pintype "passive"))
    )
    (net (code "32") (name "Net-(U6-BOOT)") (class "Default")
      (node (ref "R38") (pin "2") (pinfunction "2_2") (pintype "passive"))
      (node (ref "U6") (pin "8") (pinfunction "BOOT_8") (pintype "passive"))
    )
    (net (code "33") (name "Net-(U6-BP5)") (class "Default")
      (node (ref "C32") (pin "1") (pinfunction "1_1") (pintype "passive"))
      (node (ref "R41") (pin "2") (pinfunction "2_2") (pintype "passive"))
      (node (ref "U6") (pin "6") (pinfunction "BP5_6") (pintype "passive"))
    )
    (net (code "34") (name "Net-(U6-COMP)") (class "Default")
      (node (ref "C24") (pin "1") (pinfunction "1_1") (pintype "passive"))
      (node (ref "C30") (pin "1") (pinfunction "1_1") (pintype "passive"))
      (node (ref "R40") (pin "2") (pinfunction "2_2") (pintype "passive"))
      (node (ref "U6") (pin "3") (pinfunction "COMP_3") (pintype "passive"))
    )
    (net (code "35") (name "Net-(U6-FB)") (class "Default")
      (node (ref "C30") (pin "2") (pinfunction "2_2") (pintype "passive"))
      (node (ref "R37") (pin "1") (pinfunction "1_1") (pintype "passive"))
      (node (ref "R44") (pin "2") (pinfunction "2_2") (pintype "passive"))
      (node (ref "R45") (pin "2") (pinfunction "2_2") (pintype "passive"))
      (node (ref "R46") (pin "2") (pinfunction "2_2") (pintype "passive"))
      (node (ref "U6") (pin "2") (pinfunction "FB_2") (pintype "passive"))
    )
    (net (code "36") (name "Net-(U6-VDD)") (class "Default")
      (node (ref "C31") (pin "2") (pinfunction "2_2") (pintype "passive"))
      (node (ref "R36") (pin "1") (pinfunction "1_1") (pintype "passive"))
      (node (ref "U6") (pin "4") (pinfunction "VDD_4") (pintype "passive"))
    )
    (net (code "37") (name "VCC2V5") (class "Default")
      (node (ref "R39") (pin "2") (pinfunction "2_2") (pintype "passive"))
    )
    (net (code "38") (name "VCC12V") (class "Default")
      (node (ref "C20") (pin "2") (pinfunction "2_2") (pintype "passive"))
      (node (ref "C5") (pin "2") (pinfunction "2_2") (pintype "passive"))
      (node (ref "F1") (pin "2") (pinfunction "2_2") (pintype "passive"))
      (node (ref "R26") (pin "2") (pinfunction "2_2") (pintype "passive"))
      (node (ref "R35") (pin "2") (pinfunction "2_2") (pintype "passive"))
      (node (ref "R80") (pin "1") (pinfunction "1_1") (pintype "passive"))
      (node (ref "R81") (pin "1") (pinfunction "1_1") (pintype "passive"))
    )
    (net (code "39") (name "VCCINT1V2_A") (class "Default")
      (node (ref "C11") (pin "1") (pinfunction "1_1") (pintype "passive"))
      (node (ref "C12") (pin "1") (pinfunction "1_1") (pintype "passive"))
      (node (ref "C13") (pin "2") (pinfunction "2_2") (pintype "passive"))
      (node (ref "C14") (pin "2") (pinfunction "2_2") (pintype "passive"))
      (node (ref "C19") (pin "2") (pinfunction "2_2") (pintype "passive"))
      (node (ref "L1") (pin "2") (pinfunction "2_2") (pintype "passive"))
      (node (ref "R32") (pin "1") (pinfunction "1_1") (pintype "passive"))
      (node (ref "TP3") (pin "1") (pinfunction "TP_1") (pintype "passive"))
    )
    (net (code "40") (name "VCCINT1V2_B") (class "Default")
      (node (ref "C26") (pin "1") (pinfunction "1_1") (pintype "passive"))
      (node (ref "C27") (pin "1") (pinfunction "1_1") (pintype "passive"))
      (node (ref "C28") (pin "2") (pinfunction "2_2") (pintype "passive"))
      (node (ref "C29") (pin "2") (pinfunction "2_2") (pintype "passive"))
      (node (ref "C33") (pin "2") (pinfunction "2_2") (pintype "passive"))
      (node (ref "L2") (pin "2") (pinfunction "2_2") (pintype "passive"))
      (node (ref "R44") (pin "1") (pinfunction "1_1") (pintype "passive"))
      (node (ref "TP6") (pin "1") (pinfunction "TP_1") (pintype "passive"))
    )
    (net (code "41") (name "unconnected-(S1-Pad3)") (class "Default")
      (node (ref "S1") (pin "3") (pinfunction "3_3") (pintype "passive"))
    )
  )
)
